# 03_-_RS485.net
KiCad netlist of a schematic drawn in Altium Designer
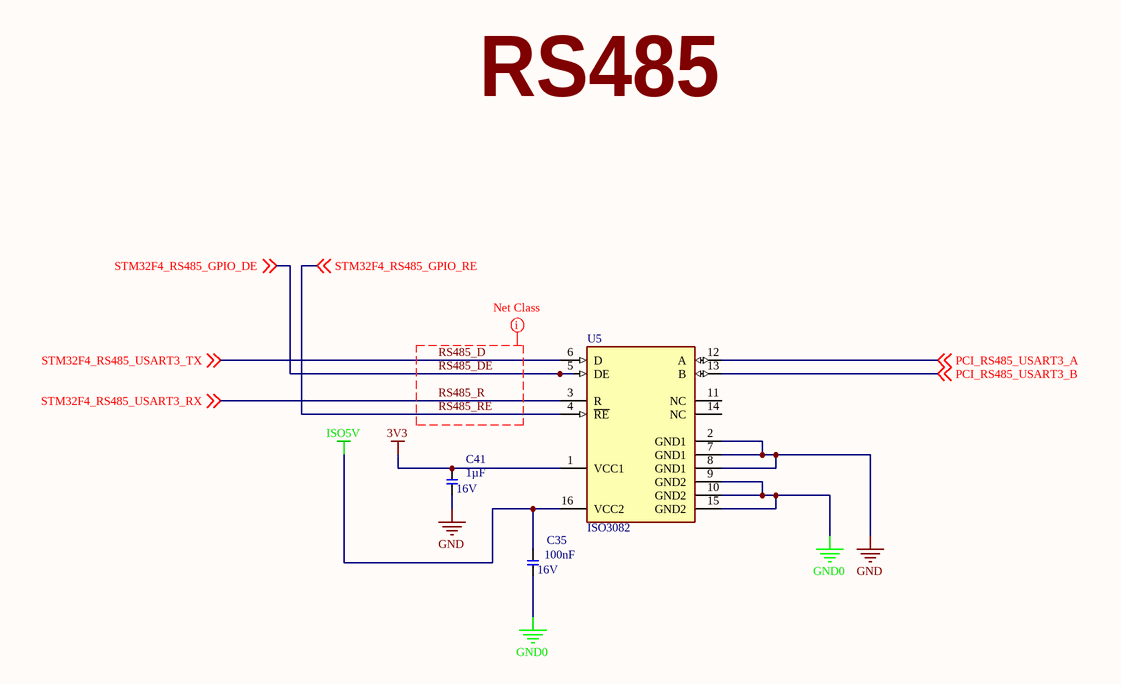
[diagram p0: [03] - RS485.SchDoc]

(export (version "E")
  (design (tool "Eeschema 10.0.6"))
  (components
    (comp (ref "C35")
      (value "100nF")
      (footprint "C0805")
      (description "AVX - 0805YA103JAT2A - CAP, MLCC, C0G/NP0, 10NF, 16V, 0805")
      (fields
        (field (name "MANUFACTURER") "AVX")
        (field (name "MANUFACTURER PART NUMBER") "0805YA103JAT2A")
        (field (name "VOLTAGE - RATED") "16V")
      )
      (libsource (lib "CPU_STM_080816") (part "C-100NF,16V,0805"))
    )
    (comp (ref "C41")
      (value "1µF")
      (footprint "C0805")
      (description "AVX - 0805YC105KAT2A - CAP, MLCC, X7R, 1UF, 16V, 0805")
      (fields
        (field (name "MANUFACTURER") "AVX Corporation")
        (field (name "MANUFACTURER PART NUMBER") "0805YC105KAT2A")
        (field (name "VOLTAGE - RATED") "16V")
      )
      (libsource (lib "CPU_STM_080816") (part "C-1UF,16V,0805"))
    )
    (comp (ref "U5")
      (value "ISO3082")
      (footprint "DW16_L")
      (description "DG ISO 2.5KV RS422/RS485 16SOIC")
      (fields
        (field (name "MANUFACTURER") "Texas Instruments")
        (field (name "MANUFACTURER PART NUMBER") "ISO3082DWR")
      )
      (libsource (lib "CPU_STM_080816") (part "IC-ISO3082-SOIC-DW-16"))
    )
  )
  (nets
    (net (code "1") (name "3V3") (class "Default")
      (node (ref "C41") (pin "2") (pinfunction "2_2") (pintype "passive"))
      (node (ref "U5") (pin "1") (pinfunction "VCC1_1") (pintype "power_in"))
    )
    (net (code "2") (name "GND") (class "Default")
      (node (ref "C41") (pin "1") (pinfunction "1_1") (pintype "passive"))
      (node (ref "U5") (pin "2") (pinfunction "GND1_2") (pintype "power_in"))
      (node (ref "U5") (pin "7") (pinfunction "GND1_7") (pintype "power_in"))
      (node (ref "U5") (pin "8") (pinfunction "GND1_8") (pintype "power_in"))
    )
    (net (code "3") (name "GND0") (class "Default")
      (node (ref "C35") (pin "1") (pinfunction "1_1") (pintype "passive"))
      (node (ref "U5") (pin "10") (pinfunction "GND2_10") (pintype "power_in"))
      (node (ref "U5") (pin "15") (pinfunction "GND2_15") (pintype "power_in"))
      (node (ref "U5") (pin "9") (pinfunction "GND2_9") (pintype "power_in"))
    )
    (net (code "4") (name "ISO5V") (class "Default")
      (node (ref "C35") (pin "2") (pinfunction "2_2") (pintype "passive"))
      (node (ref "U5") (pin "16") (pinfunction "VCC2_16") (pintype "power_in"))
    )
    (net (code "5") (name "PCI_RS485_USART3_A") (class "Default")
      (node (ref "U5") (pin "12") (pinfunction "A_12") (pintype "bidirectional"))
    )
    (net (code "6") (name "PCI_RS485_USART3_B") (class "Default")
      (node (ref "U5") (pin "13") (pinfunction "B_13") (pintype "bidirectional"))
    )
    (net (code "7") (name "STM32F4_RS485_GPIO_DE") (class "Default")
      (node (ref "U5") (pin "5") (pinfunction "DE_5") (pintype "input"))
    )
    (net (code "8") (name "STM32F4_RS485_GPIO_RE") (class "Default")
      (node (ref "U5") (pin "4") (pinfunction "~{RE}_4") (pintype "input"))
    )
    (net (code "9") (name "STM32F4_RS485_USART3_RX") (class "Default")
      (node (ref "U5") (pin "3") (pinfunction "R_3") (pintype "tri_state"))
    )
    (net (code "10") (name "STM32F4_RS485_USART3_TX") (class "Default")
      (node (ref "U5") (pin "6") (pinfunction "D_6") (pintype "input"))
    )
    (net (code "11") (name "unconnected-(U5-NC-Pad11)") (class "Default")
      (node (ref "U5") (pin "11") (pinfunction "NC_11") (pintype "passive"))
    )
    (net (code "12") (name "unconnected-(U5-NC-Pad14)") (class "Default")
      (node (ref "U5") (pin "14") (pinfunction "NC_14") (pintype "passive"))
    )
  )
)
